# Sample_Power_Supply_LM317.net
KiCad netlist of a schematic drawn in EAGLE
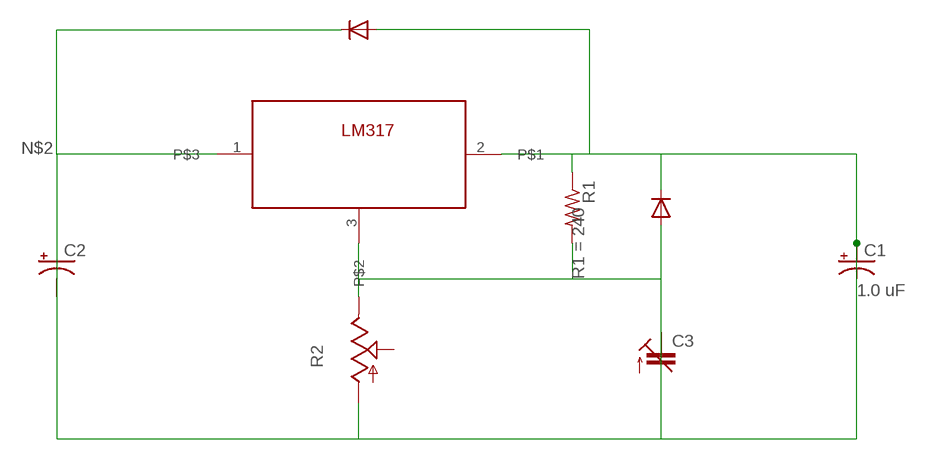
[diagram p0: schematic, sheet 1]

(export (version "E")
  (design (tool "Eeschema 10.0.6"))
  (components
    (comp (ref "C1")
      (value "CPOL-USUD-4X5,8")
      (footprint "eagle-import:UD-4X5,8_NICHICON")
      (fields (field (name "C0") "1.0 uF"))
      (libsource (lib "eagle-import") (part "CPOL-USUD-4X5,8"))
    )
    (comp (ref "C2")
      (value "CPOL-USUD-4X5,8")
      (footprint "eagle-import:UD-4X5,8_NICHICON")
      (libsource (lib "eagle-import") (part "CPOL-USUD-4X5,8"))
    )
    (comp (ref "C3")
      (value "C-TRIMMTZBX4")
      (footprint "eagle-import:CTRIMTZBX4")
      (libsource (lib "eagle-import") (part "C-TRIMMTZBX4"))
    )
    (comp (ref "R1")
      (value "R-US_R0805")
      (footprint "eagle-import:R0805")
      (fields (field (name "R1") "240"))
      (libsource (lib "eagle-import") (part "R-US_R0805"))
    )
    (comp (ref "R2")
      (value "TRIM_US-3223G")
      (footprint "eagle-import:3223G")
      (libsource (lib "eagle-import") (part "TRIM_US-3223G"))
    )
    (comp (ref "U$1")
      (value "LM317")
      (footprint "eagle-import:SOT223")
      (libsource (lib "eagle-import") (part "LM317"))
    )
  )
  (nets
    (net (code "1") (name "/N$2") (class "Default")
      (node (ref "C1") (pin "+") (pinfunction "+_+") (pintype "passive"))
      (node (ref "C1") (pin "-") (pinfunction "-_-") (pintype "passive"))
      (node (ref "C2") (pin "+") (pinfunction "+_+") (pintype "passive"))
      (node (ref "C3") (pin "1") (pinfunction "E_1") (pintype "passive"))
      (node (ref "C3") (pin "2") (pinfunction "A_2") (pintype "passive"))
      (node (ref "R1") (pin "1") (pinfunction "1_1") (pintype "passive"))
      (node (ref "R1") (pin "2") (pinfunction "2_2") (pintype "passive"))
      (node (ref "R2") (pin "1") (pinfunction "A_1") (pintype "passive"))
      (node (ref "R2") (pin "3") (pinfunction "E_3") (pintype "passive"))
    )
    (net (code "2") (name "unconnected-(C2-Pad-)") (class "Default")
      (node (ref "C2") (pin "-") (pinfunction "-_-") (pintype "passive"))
    )
    (net (code "3") (name "unconnected-(R2-S-Pad2)") (class "Default")
      (node (ref "R2") (pin "2") (pinfunction "S_2") (pintype "passive"))
    )
    (net (code "4") (name "unconnected-(U$1-P$1-Pad2)") (class "Default")
      (node (ref "U$1") (pin "2") (pinfunction "P$1_2") (pintype "bidirectional"))
    )
    (net (code "5") (name "unconnected-(U$1-P$2-Pad3)") (class "Default")
      (node (ref "U$1") (pin "3") (pinfunction "P$2_3") (pintype "bidirectional"))
    )
    (net (code "6") (name "unconnected-(U$1-P$3-Pad1)") (class "Default")
      (node (ref "U$1") (pin "1") (pinfunction "P$3_1") (pintype "bidirectional"))
    )
  )
)
